# LCR.net
KiCad netlist of a schematic drawn in EAGLE
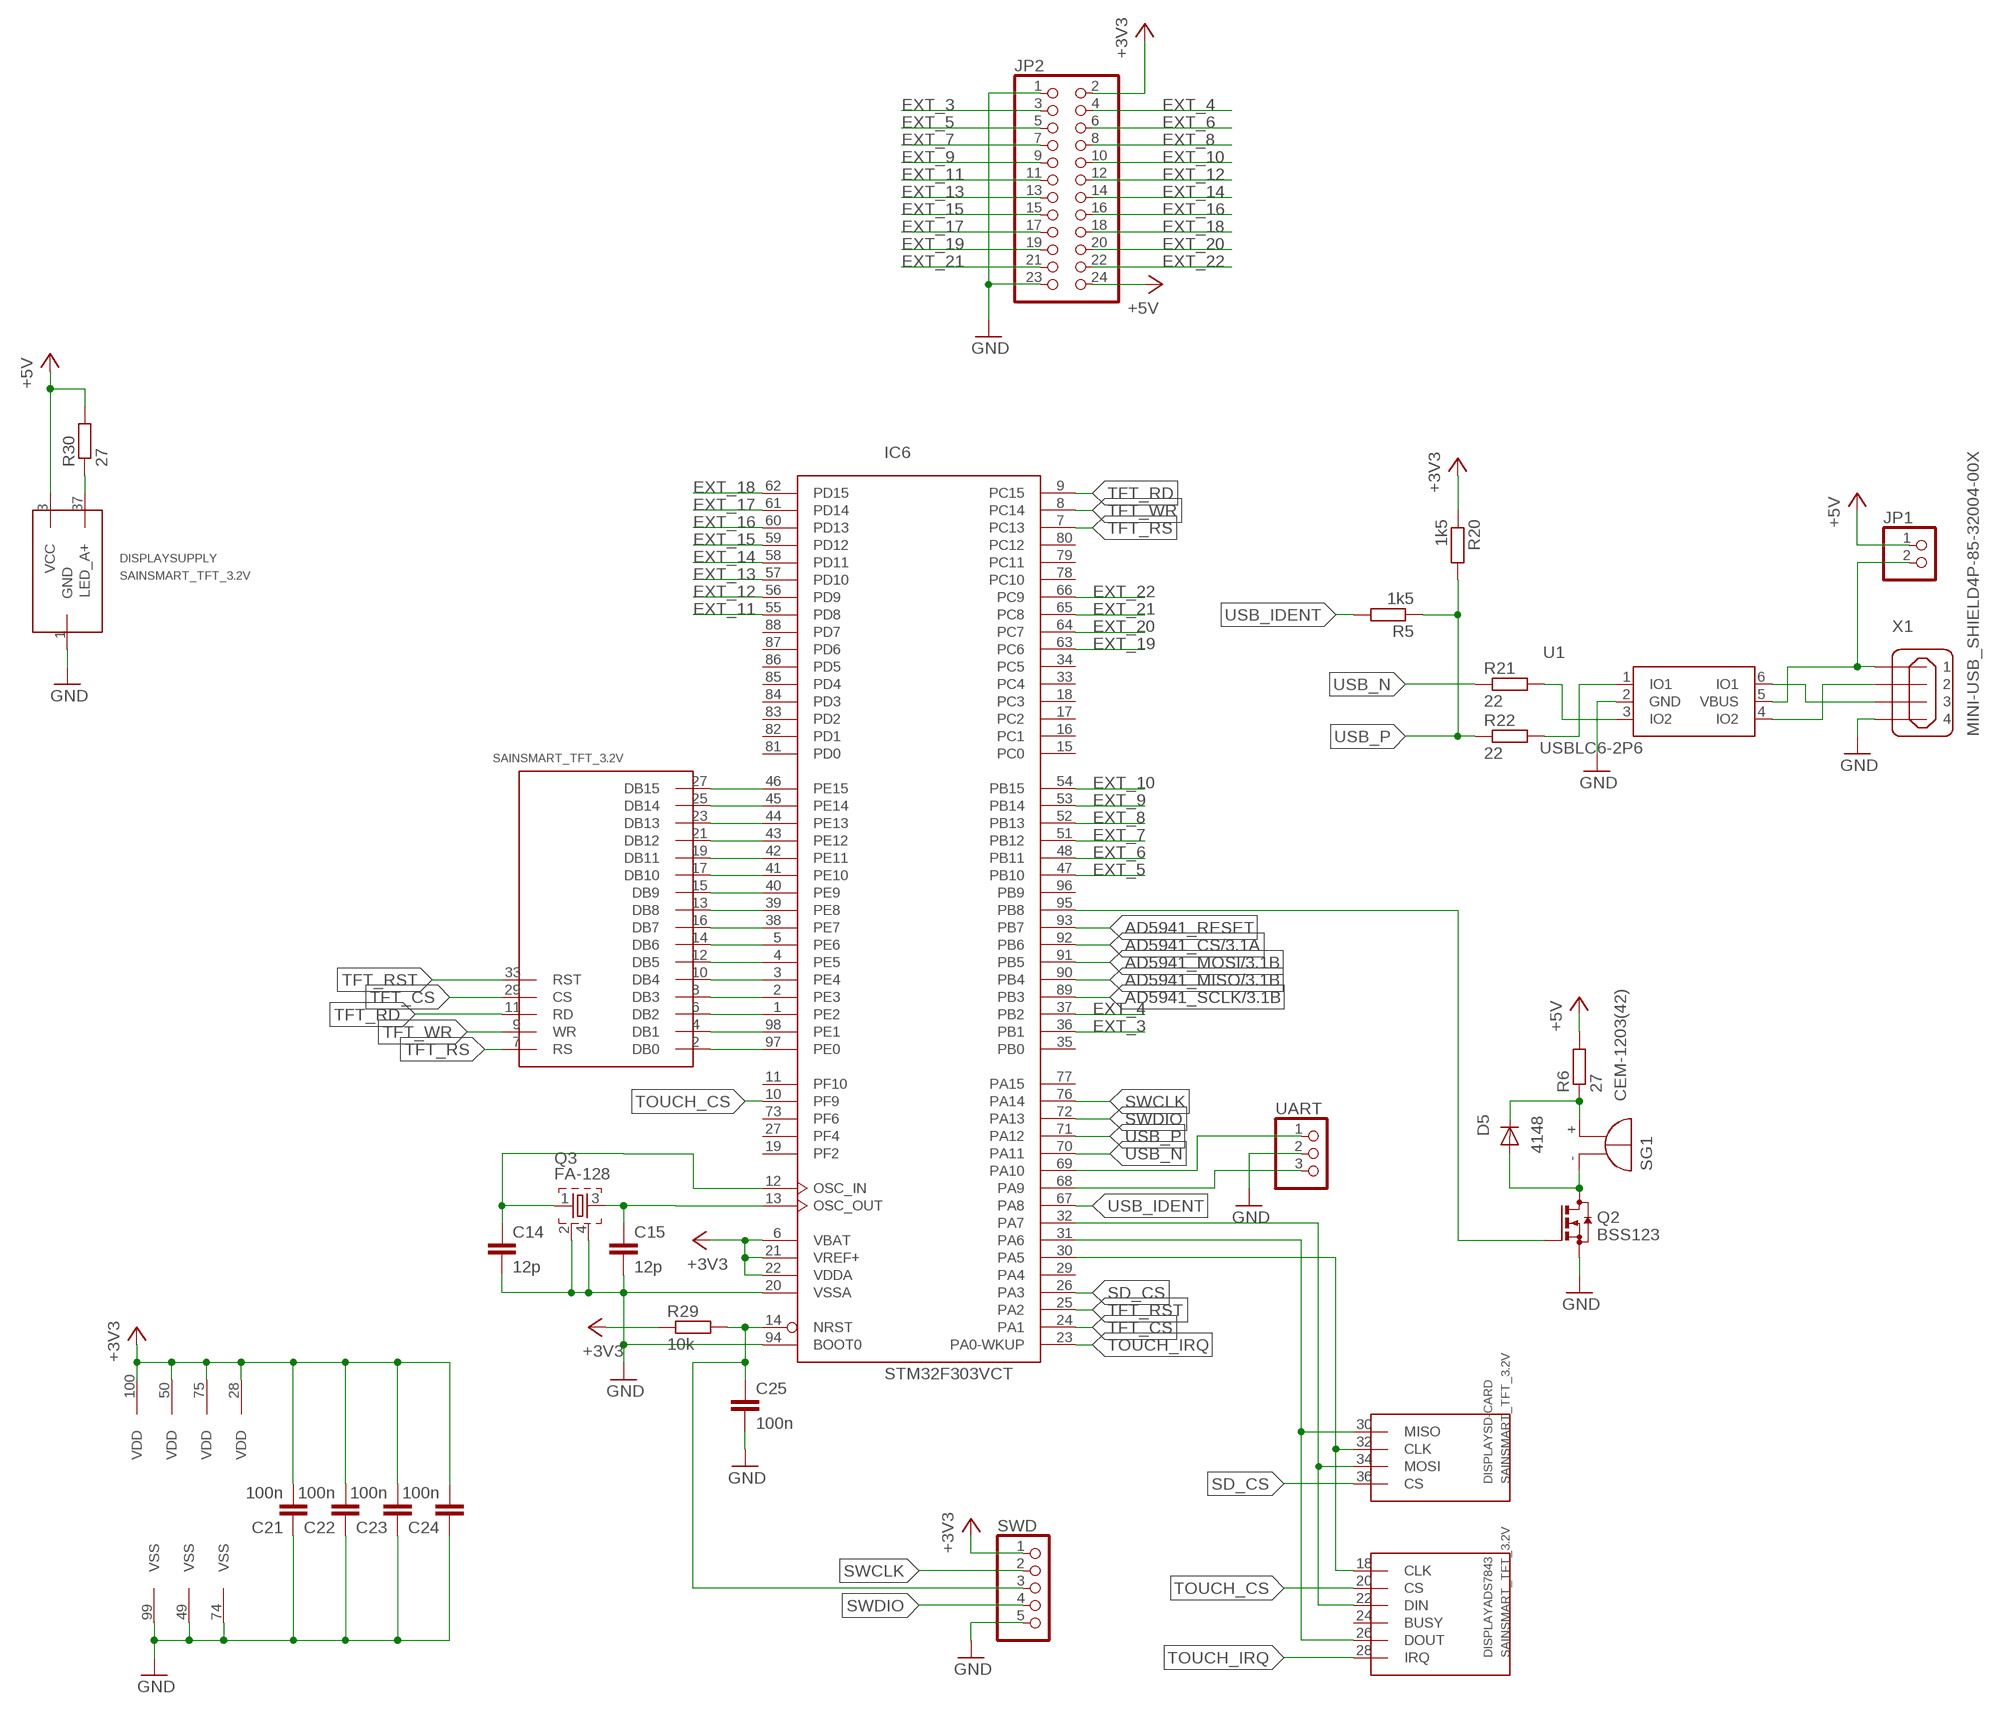
[diagram p0: schematic, sheet 1]
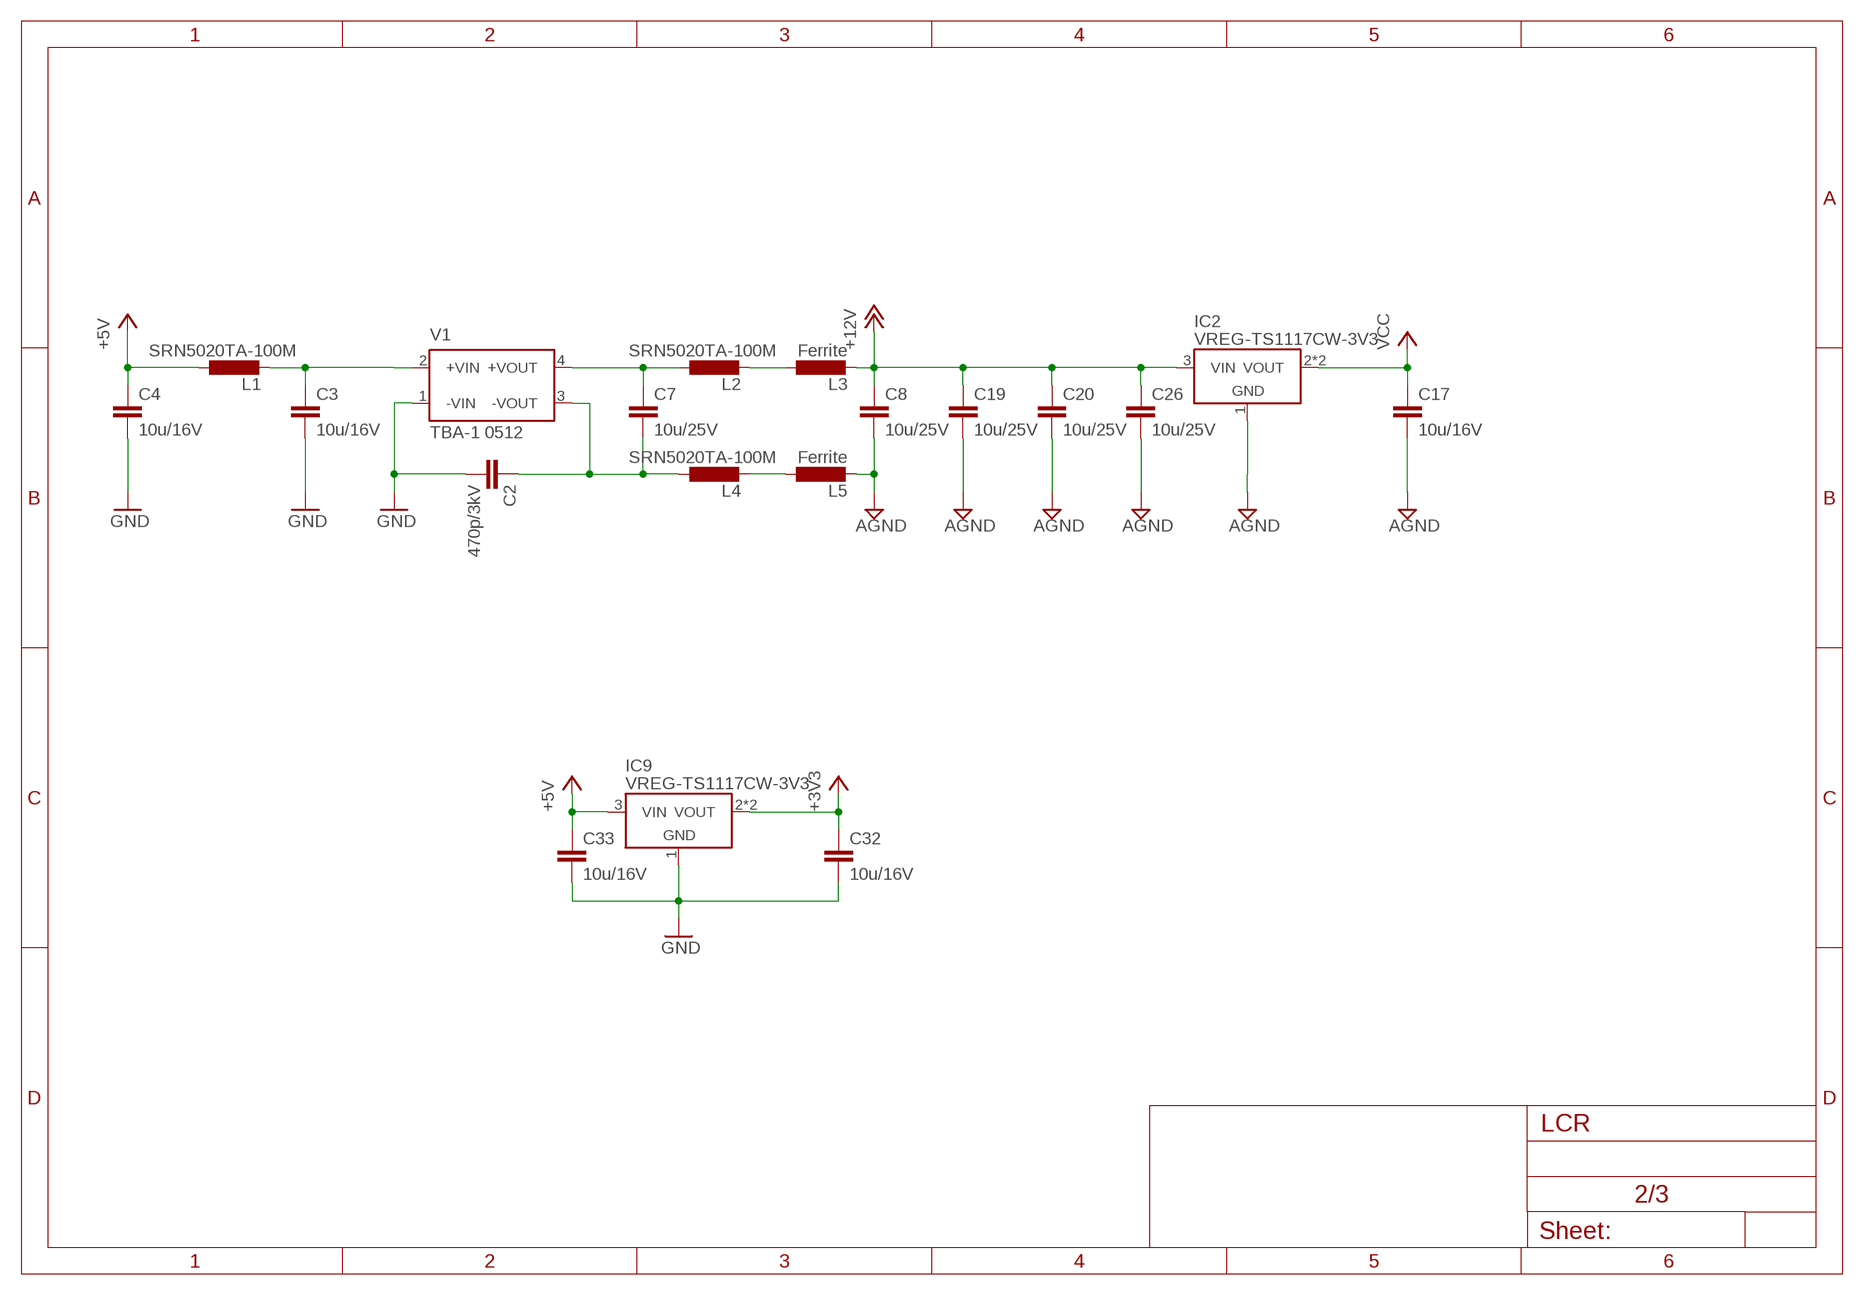
[diagram p1: schematic, sheet 2]
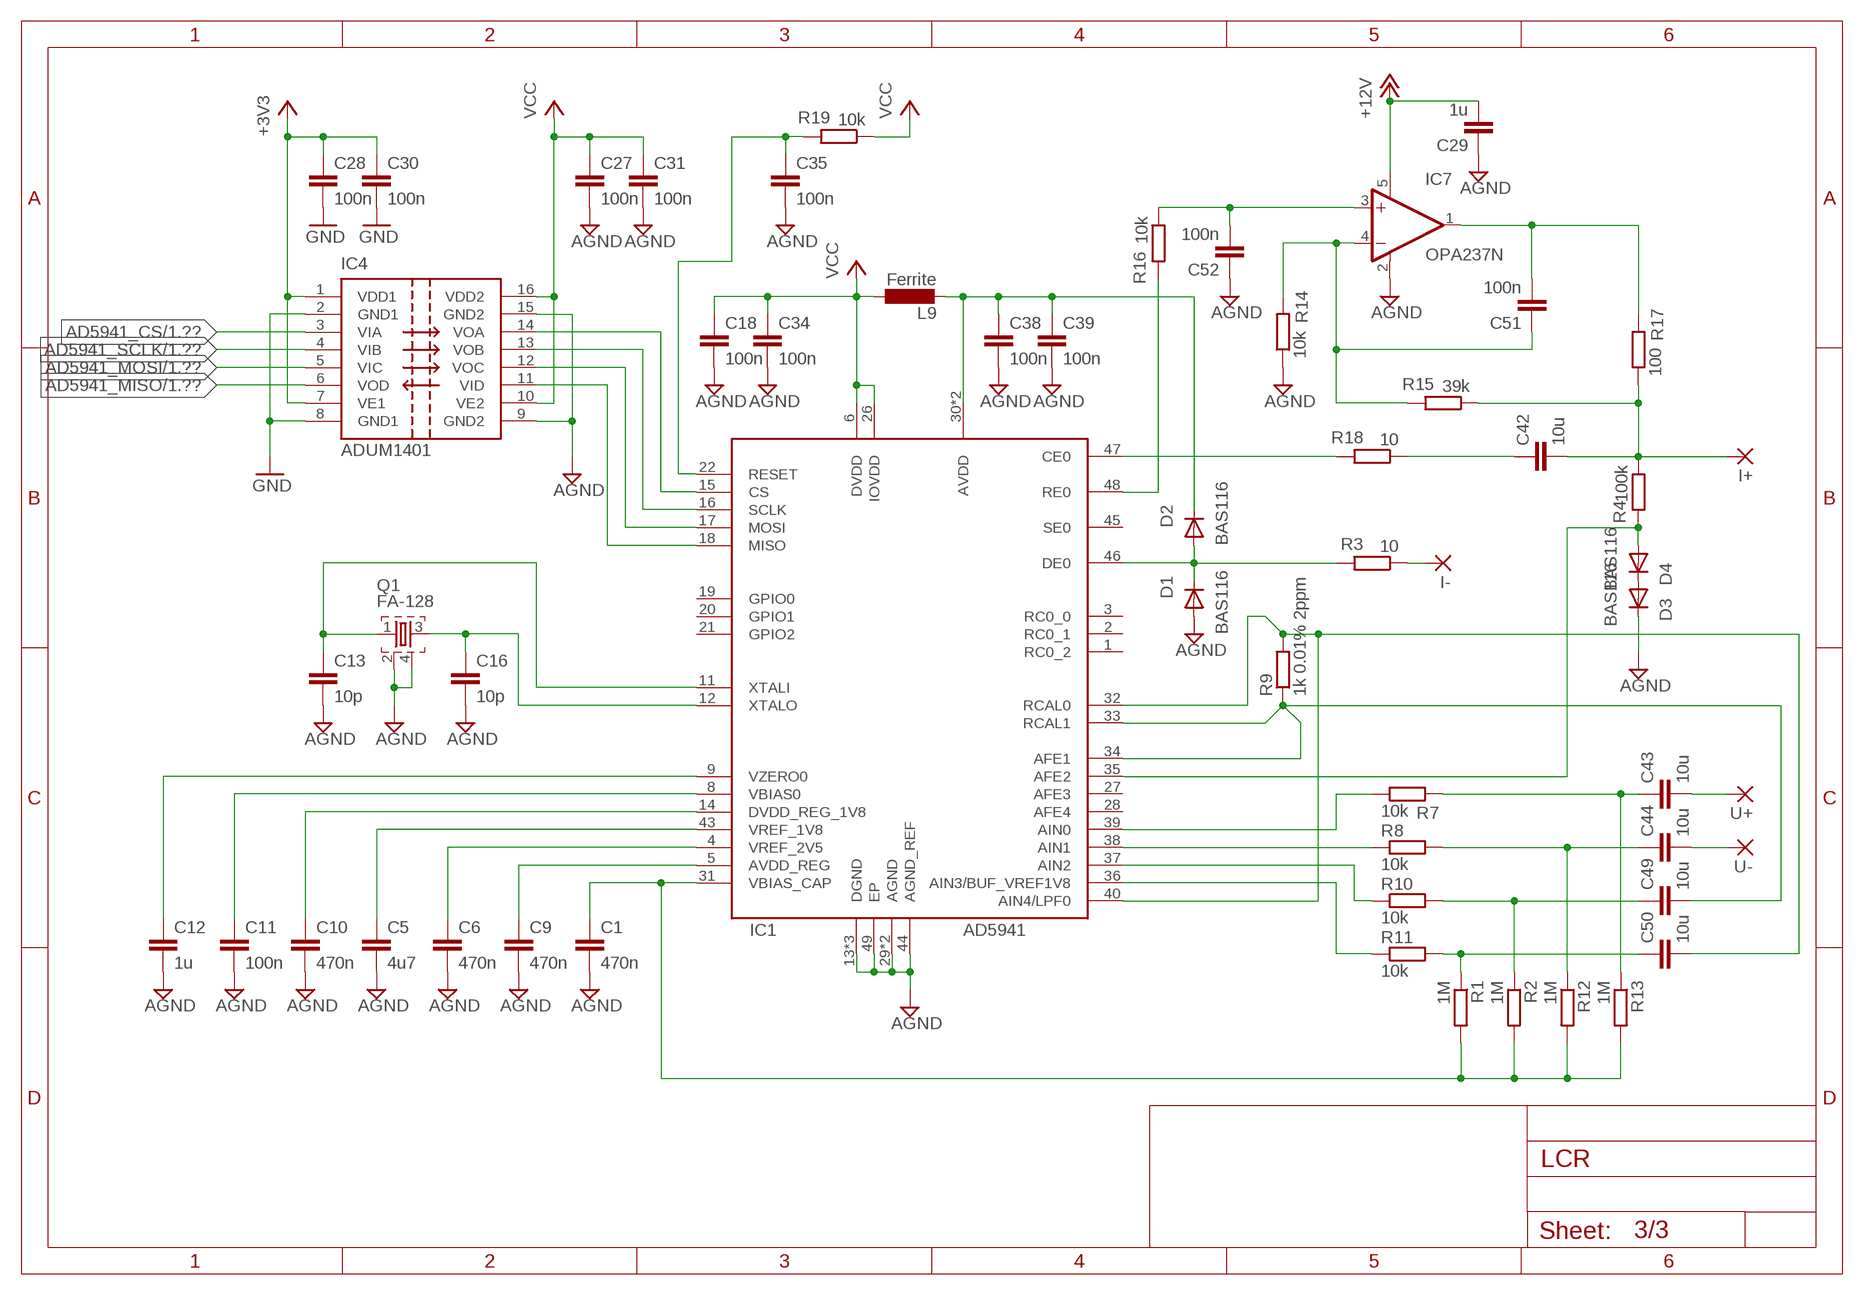
[diagram p2: schematic, sheet 3]

(export (version "E")
  (design (tool "Eeschema 10.0.6"))
  (components
    (comp (ref "C14")
      (value "12p")
      (footprint "eagle-import:C0603K")
      (libsource (lib "eagle-import") (part "C-EUC0603K"))
    )
    (comp (ref "C15")
      (value "12p")
      (footprint "eagle-import:C0603K")
      (libsource (lib "eagle-import") (part "C-EUC0603K"))
    )
    (comp (ref "C21")
      (value "100n")
      (footprint "eagle-import:C0603K")
      (libsource (lib "eagle-import") (part "C-EUC0603K"))
    )
    (comp (ref "C22")
      (value "100n")
      (footprint "eagle-import:C0603K")
      (libsource (lib "eagle-import") (part "C-EUC0603K"))
    )
    (comp (ref "C23")
      (value "100n")
      (footprint "eagle-import:C0603K")
      (libsource (lib "eagle-import") (part "C-EUC0603K"))
    )
    (comp (ref "C24")
      (value "100n")
      (footprint "eagle-import:C0603K")
      (libsource (lib "eagle-import") (part "C-EUC0603K"))
    )
    (comp (ref "C25")
      (value "100n")
      (footprint "eagle-import:C0603K")
      (libsource (lib "eagle-import") (part "C-EUC0603K"))
    )
    (comp (ref "D5")
      (value "4148")
      (footprint "eagle-import:SOD123")
      (libsource (lib "eagle-import") (part "DIODE-SOD123"))
    )
    (comp (ref "DISPLAY")
      (value "SAINSMART_TFT_3.2V")
      (footprint "eagle-import:SAINSMART_ANGLED")
      (libsource (lib "eagle-import") (part "SAINSMART_TFT_3.2V"))
    )
    (comp (ref "IC6")
      (value "STM32F303VCT")
      (footprint "eagle-import:LQFP100")
      (libsource (lib "eagle-import") (part "STM32F303VTC"))
    )
    (comp (ref "JP1")
      (value "PINHD-1X2")
      (footprint "eagle-import:1X02")
      (libsource (lib "eagle-import") (part "PINHD-1X2"))
    )
    (comp (ref "JP2")
      (value "PINHD-2X12")
      (footprint "eagle-import:2X12")
      (libsource (lib "eagle-import") (part "PINHD-2X12"))
    )
    (comp (ref "Q2")
      (value "BSS123")
      (footprint "eagle-import:SOT23")
      (libsource (lib "eagle-import") (part "BSS123"))
    )
    (comp (ref "Q3")
      (value "FA-128")
      (footprint "eagle-import:FA-128")
      (libsource (lib "eagle-import") (part "FA-128"))
    )
    (comp (ref "R5")
      (value "1k5")
      (footprint "eagle-import:R0603")
      (libsource (lib "eagle-import") (part "resistor_R-EU_R0603"))
    )
    (comp (ref "R6")
      (value "27")
      (footprint "eagle-import:R1206")
      (libsource (lib "eagle-import") (part "resistor_R-EU_R1206"))
    )
    (comp (ref "R20")
      (value "1k5")
      (footprint "eagle-import:R0603")
      (libsource (lib "eagle-import") (part "resistor_R-EU_R0603"))
    )
    (comp (ref "R21")
      (value "22")
      (footprint "eagle-import:R0603")
      (libsource (lib "eagle-import") (part "resistor_R-EU_R0603"))
    )
    (comp (ref "R22")
      (value "22")
      (footprint "eagle-import:R0603")
      (libsource (lib "eagle-import") (part "resistor_R-EU_R0603"))
    )
    (comp (ref "R29")
      (value "10k")
      (footprint "eagle-import:R0603")
      (libsource (lib "eagle-import") (part "resistor_R-EU_R0603"))
    )
    (comp (ref "R30")
      (value "27")
      (footprint "eagle-import:R1206")
      (libsource (lib "eagle-import") (part "resistor_R-EU_R1206"))
    )
    (comp (ref "SG1")
      (value "CEM-1203(42)")
      (footprint "eagle-import:F_QMBIII")
      (libsource (lib "eagle-import") (part "F/QMBIII"))
    )
    (comp (ref "SWD")
      (value "PINHD-1X5")
      (footprint "eagle-import:1X05")
      (libsource (lib "eagle-import") (part "PINHD-1X5"))
    )
    (comp (ref "U1")
      (value "USBLC6-2P6")
      (footprint "eagle-import:SOT23-6")
      (libsource (lib "eagle-import") (part "USBLC6-2P6"))
    )
    (comp (ref "UART")
      (value "PINHD-1X3")
      (footprint "eagle-import:1X03")
      (libsource (lib "eagle-import") (part "PINHD-1X3"))
    )
    (comp (ref "X1")
      (value "MINI-USB_SHIELD4P-85-32004-00X")
      (footprint "eagle-import:85-32004-00X")
      (libsource (lib "eagle-import") (part "MINI-USB_SHIELD4P-85-32004-00X"))
    )
    (comp (ref "C2")
      (value "470p/3kV")
      (footprint "eagle-import:C1812")
      (libsource (lib "eagle-import") (part "resistor_C-EUC1812"))
    )
    (comp (ref "C3")
      (value "10u/16V")
      (footprint "eagle-import:C1206K")
      (libsource (lib "eagle-import") (part "C-EUC1206K"))
    )
    (comp (ref "C4")
      (value "10u/16V")
      (footprint "eagle-import:C1206K")
      (libsource (lib "eagle-import") (part "C-EUC1206K"))
    )
    (comp (ref "C7")
      (value "10u/25V")
      (footprint "eagle-import:C1206K")
      (libsource (lib "eagle-import") (part "C-EUC1206K"))
    )
    (comp (ref "C8")
      (value "10u/25V")
      (footprint "eagle-import:C1206K")
      (libsource (lib "eagle-import") (part "C-EUC1206K"))
    )
    (comp (ref "C17")
      (value "10u/16V")
      (footprint "eagle-import:C1206K")
      (libsource (lib "eagle-import") (part "C-EUC1206K"))
    )
    (comp (ref "C19")
      (value "10u/25V")
      (footprint "eagle-import:C1206K")
      (libsource (lib "eagle-import") (part "C-EUC1206K"))
    )
    (comp (ref "C20")
      (value "10u/25V")
      (footprint "eagle-import:C1206K")
      (libsource (lib "eagle-import") (part "C-EUC1206K"))
    )
    (comp (ref "C26")
      (value "10u/25V")
      (footprint "eagle-import:C1206K")
      (libsource (lib "eagle-import") (part "C-EUC1206K"))
    )
    (comp (ref "C32")
      (value "10u/16V")
      (footprint "eagle-import:C1206K")
      (libsource (lib "eagle-import") (part "C-EUC1206K"))
    )
    (comp (ref "C33")
      (value "10u/16V")
      (footprint "eagle-import:C1206K")
      (libsource (lib "eagle-import") (part "C-EUC1206K"))
    )
    (comp (ref "IC2")
      (value "VREG-TS1117CW-3V3")
      (footprint "eagle-import:SOT223")
      (libsource (lib "eagle-import") (part "VREG-TS1117CW-3V3"))
    )
    (comp (ref "IC9")
      (value "VREG-TS1117CW-3V3")
      (footprint "eagle-import:SOT223")
      (libsource (lib "eagle-import") (part "VREG-TS1117CW-3V3"))
    )
    (comp (ref "L1")
      (value "SRN5020TA-100M")
      (footprint "eagle-import:SRN5040")
      (libsource (lib "eagle-import") (part "SRN5040"))
    )
    (comp (ref "L2")
      (value "SRN5020TA-100M")
      (footprint "eagle-import:SRN5040")
      (libsource (lib "eagle-import") (part "SRN5040"))
    )
    (comp (ref "L3")
      (value "Ferrite")
      (footprint "eagle-import:R0603")
      (libsource (lib "eagle-import") (part "INDUCTOR0603"))
    )
    (comp (ref "L4")
      (value "SRN5020TA-100M")
      (footprint "eagle-import:SRN5040")
      (libsource (lib "eagle-import") (part "SRN5040"))
    )
    (comp (ref "L5")
      (value "Ferrite")
      (footprint "eagle-import:R0603")
      (libsource (lib "eagle-import") (part "INDUCTOR0603"))
    )
    (comp (ref "V1")
      (value "TBA-1 0512")
      (footprint "eagle-import:TME")
      (fields (field (name "MPN") "TME 0505S"))
      (libsource (lib "eagle-import") (part "TME?0505S"))
    )
    (comp (ref "C1")
      (value "470n")
      (footprint "eagle-import:C0603K")
      (libsource (lib "eagle-import") (part "C-EUC0603K"))
    )
    (comp (ref "C5")
      (value "4u7")
      (footprint "eagle-import:C0603K")
      (libsource (lib "eagle-import") (part "C-EUC0603K"))
    )
    (comp (ref "C6")
      (value "470n")
      (footprint "eagle-import:C0603K")
      (libsource (lib "eagle-import") (part "C-EUC0603K"))
    )
    (comp (ref "C9")
      (value "470n")
      (footprint "eagle-import:C0603K")
      (libsource (lib "eagle-import") (part "C-EUC0603K"))
    )
    (comp (ref "C10")
      (value "470n")
      (footprint "eagle-import:C0603K")
      (libsource (lib "eagle-import") (part "C-EUC0603K"))
    )
    (comp (ref "C11")
      (value "100n")
      (footprint "eagle-import:C0603K")
      (libsource (lib "eagle-import") (part "C-EUC0603K"))
    )
    (comp (ref "C12")
      (value "1u")
      (footprint "eagle-import:C0603K")
      (libsource (lib "eagle-import") (part "C-EUC0603K"))
    )
    (comp (ref "C13")
      (value "10p")
      (footprint "eagle-import:C0603K")
      (libsource (lib "eagle-import") (part "C-EUC0603K"))
    )
    (comp (ref "C16")
      (value "10p")
      (footprint "eagle-import:C0603K")
      (libsource (lib "eagle-import") (part "C-EUC0603K"))
    )
    (comp (ref "C18")
      (value "100n")
      (footprint "eagle-import:C0603K")
      (libsource (lib "eagle-import") (part "C-EUC0603K"))
    )
    (comp (ref "C27")
      (value "100n")
      (footprint "eagle-import:C0603K")
      (libsource (lib "eagle-import") (part "C-EUC0603K"))
    )
    (comp (ref "C28")
      (value "100n")
      (footprint "eagle-import:C0603K")
      (libsource (lib "eagle-import") (part "C-EUC0603K"))
    )
    (comp (ref "C29")
      (value "1u")
      (footprint "eagle-import:C0603K")
      (libsource (lib "eagle-import") (part "C-EUC0603K"))
    )
    (comp (ref "C30")
      (value "100n")
      (footprint "eagle-import:C0603K")
      (libsource (lib "eagle-import") (part "C-EUC0603K"))
    )
    (comp (ref "C31")
      (value "100n")
      (footprint "eagle-import:C0603K")
      (libsource (lib "eagle-import") (part "C-EUC0603K"))
    )
    (comp (ref "C34")
      (value "100n")
      (footprint "eagle-import:C0603K")
      (libsource (lib "eagle-import") (part "C-EUC0603K"))
    )
    (comp (ref "C35")
      (value "100n")
      (footprint "eagle-import:C0603K")
      (libsource (lib "eagle-import") (part "C-EUC0603K"))
    )
    (comp (ref "C38")
      (value "100n")
      (footprint "eagle-import:C0603K")
      (libsource (lib "eagle-import") (part "C-EUC0603K"))
    )
    (comp (ref "C39")
      (value "100n")
      (footprint "eagle-import:C0603K")
      (libsource (lib "eagle-import") (part "C-EUC0603K"))
    )
    (comp (ref "C42")
      (value "10u")
      (footprint "eagle-import:C1206K")
      (libsource (lib "eagle-import") (part "resistor_C-EUC1206K"))
    )
    (comp (ref "C43")
      (value "10u")
      (footprint "eagle-import:C1206K")
      (libsource (lib "eagle-import") (part "resistor_C-EUC1206K"))
    )
    (comp (ref "C44")
      (value "10u")
      (footprint "eagle-import:C1206K")
      (libsource (lib "eagle-import") (part "resistor_C-EUC1206K"))
    )
    (comp (ref "C49")
      (value "10u")
      (footprint "eagle-import:C1206K")
      (libsource (lib "eagle-import") (part "resistor_C-EUC1206K"))
    )
    (comp (ref "C50")
      (value "10u")
      (footprint "eagle-import:C1206K")
      (libsource (lib "eagle-import") (part "resistor_C-EUC1206K"))
    )
    (comp (ref "C51")
      (value "100n")
      (footprint "eagle-import:C0603K")
      (libsource (lib "eagle-import") (part "C-EUC0603K"))
    )
    (comp (ref "C52")
      (value "100n")
      (footprint "eagle-import:C0603K")
      (libsource (lib "eagle-import") (part "C-EUC0603K"))
    )
    (comp (ref "D1")
      (value "BAS116")
      (footprint "eagle-import:SOD123")
      (libsource (lib "eagle-import") (part "DIODE-SOD123"))
    )
    (comp (ref "D2")
      (value "BAS116")
      (footprint "eagle-import:SOD123")
      (libsource (lib "eagle-import") (part "DIODE-SOD123"))
    )
    (comp (ref "D3")
      (value "BAS116")
      (footprint "eagle-import:SOD123")
      (libsource (lib "eagle-import") (part "DIODE-SOD123"))
    )
    (comp (ref "D4")
      (value "BAS116")
      (footprint "eagle-import:SOD123")
      (libsource (lib "eagle-import") (part "DIODE-SOD123"))
    )
    (comp (ref "I+")
      (value "2,54/1,1")
      (footprint "eagle-import:2,54_1,1")
      (libsource (lib "eagle-import") (part "2,54/1,1"))
    )
    (comp (ref "I-")
      (value "2,54/1,1")
      (footprint "eagle-import:2,54_1,1")
      (libsource (lib "eagle-import") (part "2,54/1,1"))
    )
    (comp (ref "IC1")
      (value "AD5941")
      (footprint "eagle-import:QFN50P700X700X80-49T510N")
      (libsource (lib "eagle-import") (part "AD5941"))
    )
    (comp (ref "IC4")
      (value "ADUM1401")
      (footprint "eagle-import:SO16W")
      (libsource (lib "eagle-import") (part "ADUM1401"))
    )
    (comp (ref "IC7")
      (value "OPA237N")
      (footprint "eagle-import:SOT23-5")
      (fields (field (name "MF") "TEXAS INSTRUMENTS") (field (name "MPN") "OPA237NA/250"))
      (libsource (lib "eagle-import") (part "OPA237N"))
    )
    (comp (ref "L9")
      (value "Ferrite")
      (footprint "eagle-import:R0603")
      (libsource (lib "eagle-import") (part "INDUCTOR0603"))
    )
    (comp (ref "Q1")
      (value "FA-128")
      (footprint "eagle-import:FA-128")
      (libsource (lib "eagle-import") (part "FA-128"))
    )
    (comp (ref "R1")
      (value "1M")
      (footprint "eagle-import:R0603")
      (libsource (lib "eagle-import") (part "R-EU_R0603"))
    )
    (comp (ref "R2")
      (value "1M")
      (footprint "eagle-import:R0603")
      (libsource (lib "eagle-import") (part "R-EU_R0603"))
    )
    (comp (ref "R3")
      (value "10")
      (footprint "eagle-import:R0603")
      (libsource (lib "eagle-import") (part "R-EU_R0603"))
    )
    (comp (ref "R4")
      (value "100k")
      (footprint "eagle-import:R0603")
      (libsource (lib "eagle-import") (part "R-EU_R0603"))
    )
    (comp (ref "R7")
      (value "10k")
      (footprint "eagle-import:R0603")
      (libsource (lib "eagle-import") (part "R-EU_R0603"))
    )
    (comp (ref "R8")
      (value "10k")
      (footprint "eagle-import:R0603")
      (libsource (lib "eagle-import") (part "R-EU_R0603"))
    )
    (comp (ref "R9")
      (value "1k 0.01% 2ppm")
      (footprint "eagle-import:M0805")
      (libsource (lib "eagle-import") (part "resistor_R-EU_M0805"))
    )
    (comp (ref "R10")
      (value "10k")
      (footprint "eagle-import:R0603")
      (libsource (lib "eagle-import") (part "R-EU_R0603"))
    )
    (comp (ref "R11")
      (value "10k")
      (footprint "eagle-import:R0603")
      (libsource (lib "eagle-import") (part "R-EU_R0603"))
    )
    (comp (ref "R12")
      (value "1M")
      (footprint "eagle-import:R0603")
      (libsource (lib "eagle-import") (part "R-EU_R0603"))
    )
    (comp (ref "R13")
      (value "1M")
      (footprint "eagle-import:R0603")
      (libsource (lib "eagle-import") (part "R-EU_R0603"))
    )
    (comp (ref "R14")
      (value "10k")
      (footprint "eagle-import:R0603")
      (libsource (lib "eagle-import") (part "R-EU_R0603"))
    )
    (comp (ref "R15")
      (value "39k")
      (footprint "eagle-import:R0603")
      (libsource (lib "eagle-import") (part "R-EU_R0603"))
    )
    (comp (ref "R16")
      (value "10k")
      (footprint "eagle-import:R0603")
      (libsource (lib "eagle-import") (part "R-EU_R0603"))
    )
    (comp (ref "R17")
      (value "100")
      (footprint "eagle-import:R0603")
      (libsource (lib "eagle-import") (part "R-EU_R0603"))
    )
    (comp (ref "R18")
      (value "10")
      (footprint "eagle-import:R0603")
      (libsource (lib "eagle-import") (part "R-EU_R0603"))
    )
    (comp (ref "R19")
      (value "10k")
      (footprint "eagle-import:R0603")
      (libsource (lib "eagle-import") (part "R-EU_R0603"))
    )
    (comp (ref "U+")
      (value "2,54/1,1")
      (footprint "eagle-import:2,54_1,1")
      (libsource (lib "eagle-import") (part "2,54/1,1"))
    )
    (comp (ref "U-")
      (value "2,54/1,1")
      (footprint "eagle-import:2,54_1,1")
      (libsource (lib "eagle-import") (part "2,54/1,1"))
    )
  )
  (nets
    (net (code "1") (name "+3V3") (class "Default")
      (node (ref "C21") (pin "2") (pinfunction "2_2") (pintype "passive"))
      (node (ref "C22") (pin "2") (pinfunction "2_2") (pintype "passive"))
      (node (ref "C23") (pin "2") (pinfunction "2_2") (pintype "passive"))
      (node (ref "C24") (pin "2") (pinfunction "2_2") (pintype "passive"))
      (node (ref "C28") (pin "1") (pinfunction "1_1") (pintype "passive"))
      (node (ref "C30") (pin "1") (pinfunction "1_1") (pintype "passive"))
      (node (ref "C32") (pin "1") (pinfunction "1_1") (pintype "passive"))
      (node (ref "IC4") (pin "1") (pinfunction "VDD1_1") (pintype "power_in"))
      (node (ref "IC4") (pin "7") (pinfunction "VE1_7") (pintype "passive"))
      (node (ref "IC6") (pin "100") (pinfunction "VDD_100") (pintype "power_in"))
      (node (ref "IC6") (pin "21") (pinfunction "VREF+_21") (pintype "power_in"))
      (node (ref "IC6") (pin "22") (pinfunction "VDDA_22") (pintype "power_in"))
      (node (ref "IC6") (pin "28") (pinfunction "VDD_28") (pintype "power_in"))
      (node (ref "IC6") (pin "50") (pinfunction "VDD_50") (pintype "power_in"))
      (node (ref "IC6") (pin "6") (pinfunction "VBAT_6") (pintype "power_in"))
      (node (ref "IC6") (pin "75") (pinfunction "VDD_75") (pintype "power_in"))
      (node (ref "IC9") (pin "2") (pinfunction "VOUT_2") (pintype "power_in"))
      (node (ref "IC9") (pin "4") (pinfunction "VOUT_4") (pintype "power_in"))
      (node (ref "JP2") (pin "2") (pinfunction "2_2") (pintype "passive"))
      (node (ref "R20") (pin "1") (pinfunction "1_1") (pintype "passive"))
      (node (ref "R29") (pin "1") (pinfunction "1_1") (pintype "passive"))
      (node (ref "SWD") (pin "1") (pinfunction "1_1") (pintype "passive"))
    )
    (net (code "2") (name "+5V") (class "Default")
      (node (ref "C33") (pin "1") (pinfunction "1_1") (pintype "passive"))
      (node (ref "C4") (pin "1") (pinfunction "1_1") (pintype "passive"))
      (node (ref "DISPLAY") (pin "3") (pinfunction "VCC_3") (pintype "bidirectional"))
      (node (ref "IC9") (pin "3") (pinfunction "VIN_3") (pintype "power_in"))
      (node (ref "JP1") (pin "1") (pinfunction "1_1") (pintype "passive"))
      (node (ref "JP2") (pin "24") (pinfunction "24_24") (pintype "passive"))
      (node (ref "L1") (pin "P$1") (pinfunction "1_P$1") (pintype "passive"))
      (node (ref "R30") (pin "2") (pinfunction "2_2") (pintype "passive"))
      (node (ref "R6") (pin "2") (pinfunction "2_2") (pintype "passive"))
    )
    (net (code "3") (name "+12V") (class "Default")
      (node (ref "C19") (pin "1") (pinfunction "1_1") (pintype "passive"))
      (node (ref "C20") (pin "1") (pinfunction "1_1") (pintype "passive"))
      (node (ref "C26") (pin "1") (pinfunction "1_1") (pintype "passive"))
      (node (ref "C29") (pin "2") (pinfunction "2_2") (pintype "passive"))
      (node (ref "C8") (pin "1") (pinfunction "1_1") (pintype "passive"))
      (node (ref "IC2") (pin "3") (pinfunction "VIN_3") (pintype "power_in"))
      (node (ref "IC7") (pin "5") (pinfunction "V+_5") (pintype "power_in"))
      (node (ref "L3") (pin "2") (pinfunction "2_2") (pintype "passive"))
    )
    (net (code "4") (name "AD5941_CS") (class "Default")
      (node (ref "IC4") (pin "3") (pinfunction "VIA_3") (pintype "input"))
      (node (ref "IC6") (pin "92") (pinfunction "PB6_92") (pintype "bidirectional"))
    )
    (net (code "5") (name "AD5941_MISO") (class "Default")
      (node (ref "IC4") (pin "6") (pinfunction "VOD_6") (pintype "output"))
      (node (ref "IC6") (pin "90") (pinfunction "PB4_90") (pintype "bidirectional"))
    )
    (net (code "6") (name "AD5941_MOSI") (class "Default")
      (node (ref "IC4") (pin "5") (pinfunction "VIC_5") (pintype "input"))
      (node (ref "IC6") (pin "91") (pinfunction "PB5_91") (pintype "bidirectional"))
    )
    (net (code "7") (name "AD5941_RESET") (class "Default")
      (node (ref "IC6") (pin "93") (pinfunction "PB7_93") (pintype "bidirectional"))
    )
    (net (code "8") (name "AD5941_SCLK") (class "Default")
      (node (ref "IC4") (pin "4") (pinfunction "VIB_4") (pintype "input"))
      (node (ref "IC6") (pin "89") (pinfunction "PB3_89") (pintype "bidirectional"))
    )
    (net (code "9") (name "AGND") (class "Default")
      (node (ref "C1") (pin "2") (pinfunction "2_2") (pintype "passive"))
      (node (ref "C10") (pin "2") (pinfunction "2_2") (pintype "passive"))
      (node (ref "C11") (pin "2") (pinfunction "2_2") (pintype "passive"))
      (node (ref "C12") (pin "2") (pinfunction "2_2") (pintype "passive"))
      (node (ref "C13") (pin "2") (pinfunction "2_2") (pintype "passive"))
      (node (ref "C16") (pin "2") (pinfunction "2_2") (pintype "passive"))
      (node (ref "C17") (pin "2") (pinfunction "2_2") (pintype "passive"))
      (node (ref "C18") (pin "2") (pinfunction "2_2") (pintype "passive"))
      (node (ref "C19") (pin "2") (pinfunction "2_2") (pintype "passive"))
      (node (ref "C20") (pin "2") (pinfunction "2_2") (pintype "passive"))
      (node (ref "C26") (pin "2") (pinfunction "2_2") (pintype "passive"))
      (node (ref "C27") (pin "2") (pinfunction "2_2") (pintype "passive"))
      (node (ref "C29") (pin "1") (pinfunction "1_1") (pintype "passive"))
      (node (ref "C31") (pin "2") (pinfunction "2_2") (pintype "passive"))
      (node (ref "C34") (pin "2") (pinfunction "2_2") (pintype "passive"))
      (node (ref "C35") (pin "2") (pinfunction "2_2") (pintype "passive"))
      (node (ref "C38") (pin "2") (pinfunction "2_2") (pintype "passive"))
      (node (ref "C39") (pin "2") (pinfunction "2_2") (pintype "passive"))
      (node (ref "C5") (pin "2") (pinfunction "2_2") (pintype "passive"))
      (node (ref "C52") (pin "1") (pinfunction "1_1") (pintype "passive"))
      (node (ref "C6") (pin "2") (pinfunction "2_2") (pintype "passive"))
      (node (ref "C8") (pin "2") (pinfunction "2_2") (pintype "passive"))
      (node (ref "C9") (pin "2") (pinfunction "2_2") (pintype "passive"))
      (node (ref "D1") (pin "A") (pinfunction "A_A") (pintype "passive"))
      (node (ref "D3") (pin "C") (pinfunction "C_C") (pintype "passive"))
      (node (ref "IC1") (pin "13") (pinfunction "DGND_13") (pintype "bidirectional"))
      (node (ref "IC1") (pin "23") (pinfunction "DGND_23") (pintype "bidirectional"))
      (node (ref "IC1") (pin "25") (pinfunction "DGND_25") (pintype "bidirectional"))
      (node (ref "IC1") (pin "29") (pinfunction "AGND_29") (pintype "bidirectional"))
      (node (ref "IC1") (pin "42") (pinfunction "AGND_42") (pintype "bidirectional"))
      (node (ref "IC1") (pin "44") (pinfunction "AGND_REF_44") (pintype "bidirectional"))
      (node (ref "IC1") (pin "49") (pinfunction "EP_49") (pintype "bidirectional"))
      (node (ref "IC2") (pin "1") (pinfunction "GND_1") (pintype "power_in"))
      (node (ref "IC4") (pin "15") (pinfunction "GND2_15") (pintype "power_in"))
      (node (ref "IC4") (pin "9") (pinfunction "GND2_9") (pintype "power_in"))
      (node (ref "IC7") (pin "2") (pinfunction "V-_2") (pintype "power_in"))
      (node (ref "L5") (pin "2") (pinfunction "2_2") (pintype "passive"))
      (node (ref "Q1") (pin "2") (pinfunction "2_2") (pintype "passive"))
      (node (ref "Q1") (pin "4") (pinfunction "4_4") (pintype "passive"))
      (node (ref "R14") (pin "1") (pinfunction "1_1") (pintype "passive"))
    )
    (net (code "10") (name "EXT_3") (class "Default")
      (node (ref "IC6") (pin "36") (pinfunction "PB1_36") (pintype "bidirectional"))
      (node (ref "JP2") (pin "3") (pinfunction "3_3") (pintype "passive"))
    )
    (net (code "11") (name "EXT_4") (class "Default")
      (node (ref "IC6") (pin "37") (pinfunction "PB2_37") (pintype "bidirectional"))
      (node (ref "JP2") (pin "4") (pinfunction "4_4") (pintype "passive"))
    )
    (net (code "12") (name "EXT_5") (class "Default")
      (node (ref "IC6") (pin "47") (pinfunction "PB10_47") (pintype "bidirectional"))
      (node (ref "JP2") (pin "5") (pinfunction "5_5") (pintype "passive"))
    )
    (net (code "13") (name "EXT_6") (class "Default")
      (node (ref "IC6") (pin "48") (pinfunction "PB11_48") (pintype "bidirectional"))
      (node (ref "JP2") (pin "6") (pinfunction "6_6") (pintype "passive"))
    )
    (net (code "14") (name "EXT_7") (class "Default")
      (node (ref "IC6") (pin "51") (pinfunction "PB12_51") (pintype "bidirectional"))
      (node (ref "JP2") (pin "7") (pinfunction "7_7") (pintype "passive"))
    )
    (net (code "15") (name "EXT_8") (class "Default")
      (node (ref "IC6") (pin "52") (pinfunction "PB13_52") (pintype "bidirectional"))
      (node (ref "JP2") (pin "8") (pinfunction "8_8") (pintype "passive"))
    )
    (net (code "16") (name "EXT_9") (class "Default")
      (node (ref "IC6") (pin "53") (pinfunction "PB14_53") (pintype "bidirectional"))
      (node (ref "JP2") (pin "9") (pinfunction "9_9") (pintype "passive"))
    )
    (net (code "17") (name "EXT_10") (class "Default")
      (node (ref "IC6") (pin "54") (pinfunction "PB15_54") (pintype "bidirectional"))
      (node (ref "JP2") (pin "10") (pinfunction "10_10") (pintype "passive"))
    )
    (net (code "18") (name "EXT_11") (class "Default")
      (node (ref "IC6") (pin "55") (pinfunction "PD8_55") (pintype "bidirectional"))
      (node (ref "JP2") (pin "11") (pinfunction "11_11") (pintype "passive"))
    )
    (net (code "19") (name "EXT_12") (class "Default")
      (node (ref "IC6") (pin "56") (pinfunction "PD9_56") (pintype "bidirectional"))
      (node (ref "JP2") (pin "12") (pinfunction "12_12") (pintype "passive"))
    )
    (net (code "20") (name "EXT_13") (class "Default")
      (node (ref "IC6") (pin "57") (pinfunction "PD10_57") (pintype "bidirectional"))
      (node (ref "JP2") (pin "13") (pinfunction "13_13") (pintype "passive"))
    )
    (net (code "21") (name "EXT_14") (class "Default")
      (node (ref "IC6") (pin "58") (pinfunction "PD11_58") (pintype "bidirectional"))
      (node (ref "JP2") (pin "14") (pinfunction "14_14") (pintype "passive"))
    )
    (net (code "22") (name "EXT_15") (class "Default")
      (node (ref "IC6") (pin "59") (pinfunction "PD12_59") (pintype "bidirectional"))
      (node (ref "JP2") (pin "15") (pinfunction "15_15") (pintype "passive"))
    )
    (net (code "23") (name "EXT_16") (class "Default")
      (node (ref "IC6") (pin "60") (pinfunction "PD13_60") (pintype "bidirectional"))
      (node (ref "JP2") (pin "16") (pinfunction "16_16") (pintype "passive"))
    )
    (net (code "24") (name "EXT_17") (class "Default")
      (node (ref "IC6") (pin "61") (pinfunction "PD14_61") (pintype "bidirectional"))
      (node (ref "JP2") (pin "17") (pinfunction "17_17") (pintype "passive"))
    )
    (net (code "25") (name "EXT_18") (class "Default")
      (node (ref "IC6") (pin "62") (pinfunction "PD15_62") (pintype "bidirectional"))
      (node (ref "JP2") (pin "18") (pinfunction "18_18") (pintype "passive"))
    )
    (net (code "26") (name "EXT_19") (class "Default")
      (node (ref "IC6") (pin "63") (pinfunction "PC6_63") (pintype "bidirectional"))
      (node (ref "JP2") (pin "19") (pinfunction "19_19") (pintype "passive"))
    )
    (net (code "27") (name "EXT_20") (class "Default")
      (node (ref "IC6") (pin "64") (pinfunction "PC7_64") (pintype "bidirectional"))
      (node (ref "JP2") (pin "20") (pinfunction "20_20") (pintype "passive"))
    )
    (net (code "28") (name "EXT_21") (class "Default")
      (node (ref "IC6") (pin "65") (pinfunction "PC8_65") (pintype "bidirectional"))
      (node (ref "JP2") (pin "21") (pinfunction "21_21") (pintype "passive"))
    )
    (net (code "29") (name "EXT_22") (class "Default")
      (node (ref "IC6") (pin "66") (pinfunction "PC9_66") (pintype "bidirectional"))
      (node (ref "JP2") (pin "22") (pinfunction "22_22") (pintype "passive"))
    )
    (net (code "30") (name "GND") (class "Default")
      (node (ref "C14") (pin "2") (pinfunction "2_2") (pintype "passive"))
      (node (ref "C15") (pin "2") (pinfunction "2_2") (pintype "passive"))
      (node (ref "C2") (pin "2") (pinfunction "2_2") (pintype "passive"))
      (node (ref "C21") (pin "1") (pinfunction "1_1") (pintype "passive"))
      (node (ref "C22") (pin "1") (pinfunction "1_1") (pintype "passive"))
      (node (ref "C23") (pin "1") (pinfunction "1_1") (pintype "passive"))
      (node (ref "C24") (pin "1") (pinfunction "1_1") (pintype "passive"))
      (node (ref "C25") (pin "2") (pinfunction "2_2") (pintype "passive"))
      (node (ref "C28") (pin "2") (pinfunction "2_2") (pintype "passive"))
      (node (ref "C3") (pin "2") (pinfunction "2_2") (pintype "passive"))
      (node (ref "C30") (pin "2") (pinfunction "2_2") (pintype "passive"))
      (node (ref "C32") (pin "2") (pinfunction "2_2") (pintype "passive"))
      (node (ref "C33") (pin "2") (pinfunction "2_2") (pintype "passive"))
      (node (ref "C4") (pin "2") (pinfunction "2_2") (pintype "passive"))
      (node (ref "DISPLAY") (pin "1") (pinfunction "GND_1") (pintype "bidirectional"))
      (node (ref "IC4") (pin "2") (pinfunction "GND1_2") (pintype "power_in"))
      (node (ref "IC4") (pin "8") (pinfunction "GND1_8") (pintype "power_in"))
      (node (ref "IC6") (pin "20") (pinfunction "VSSA_20") (pintype "power_in"))
      (node (ref "IC6") (pin "49") (pinfunction "VSS_49") (pintype "power_in"))
      (node (ref "IC6") (pin "74") (pinfunction "VSS_74") (pintype "power_in"))
      (node (ref "IC6") (pin "94") (pinfunction "BOOT0_94") (pintype "input"))
      (node (ref "IC6") (pin "99") (pinfunction "VSS_99") (pintype "power_in"))
      (node (ref "IC9") (pin "1") (pinfunction "GND_1") (pintype "power_in"))
      (node (ref "JP2") (pin "1") (pinfunction "1_1") (pintype "passive"))
      (node (ref "JP2") (pin "23") (pinfunction "23_23") (pintype "passive"))
      (node (ref "Q2") (pin "2") (pinfunction "S_2") (pintype "passive"))
      (node (ref "Q3") (pin "2") (pinfunction "2_2") (pintype "passive"))
      (node (ref "Q3") (pin "4") (pinfunction "4_4") (pintype "passive"))
      (node (ref "SWD") (pin "5") (pinfunction "5_5") (pintype "passive"))
      (node (ref "U1") (pin "2") (pinfunction "GND_2") (pintype "power_in"))
      (node (ref "UART") (pin "2") (pinfunction "2_2") (pintype "passive"))
      (node (ref "V1") (pin "1") (pinfunction "-VIN_1") (pintype "passive"))
      (node (ref "X1") (pin "4") (pinfunction "4_4") (pintype "passive"))
    )
    (net (code "31") (name "N$12") (class "Default")
      (node (ref "C35") (pin "1") (pinfunction "1_1") (pintype "passive"))
      (node (ref "IC1") (pin "22") (pinfunction "RESET_22") (pintype "bidirectional"))
      (node (ref "R19") (pin "2") (pinfunction "2_2") (pintype "passive"))
    )
    (net (code "32") (name "Net-(C38-Pad1)") (class "Default")
      (node (ref "C38") (pin "1") (pinfunction "1_1") (pintype "passive"))
      (node (ref "C39") (pin "1") (pinfunction "1_1") (pintype "passive"))
      (node (ref "D2") (pin "C") (pinfunction "C_C") (pintype "passive"))
      (node (ref "IC1") (pin "30") (pinfunction "AVDD_30") (pintype "bidirectional"))
      (node (ref "IC1") (pin "41") (pinfunction "AVDD_41") (pintype "bidirectional"))
      (node (ref "L9") (pin "2") (pinfunction "2_2") (pintype "passive"))
    )
    (net (code "33") (name "Net-(C42-Pad1)") (class "Default")
      (node (ref "C42") (pin "1") (pinfunction "1_1") (pintype "passive"))
      (node (ref "R18") (pin "1") (pinfunction "1_1") (pintype "passive"))
    )
    (net (code "34") (name "Net-(C43-Pad1)") (class "Default")
      (node (ref "C43") (pin "1") (pinfunction "1_1") (pintype "passive"))
      (node (ref "R13") (pin "1") (pinfunction "1_1") (pintype "passive"))
      (node (ref "R7") (pin "2") (pinfunction "2_2") (pintype "passive"))
    )
    (net (code "35") (name "Net-(C44-Pad1)") (class "Default")
      (node (ref "C44") (pin "1") (pinfunction "1_1") (pintype "passive"))
      (node (ref "R12") (pin "1") (pinfunction "1_1") (pintype "passive"))
      (node (ref "R8") (pin "2") (pinfunction "2_2") (pintype "passive"))
    )
    (net (code "36") (name "Net-(C49-Pad1)") (class "Default")
      (node (ref "C49") (pin "1") (pinfunction "1_1") (pintype "passive"))
      (node (ref "R10") (pin "2") (pinfunction "2_2") (pintype "passive"))
      (node (ref "R2") (pin "1") (pinfunction "1_1") (pintype "passive"))
    )
    (net (code "37") (name "Net-(C50-Pad1)") (class "Default")
      (node (ref "C50") (pin "1") (pinfunction "1_1") (pintype "passive"))
      (node (ref "R1") (pin "1") (pinfunction "1_1") (pintype "passive"))
      (node (ref "R11") (pin "2") (pinfunction "2_2") (pintype "passive"))
    )
    (net (code "38") (name "Net-(D3-PadA)") (class "Default")
      (node (ref "D3") (pin "A") (pinfunction "A_A") (pintype "passive"))
      (node (ref "D4") (pin "C") (pinfunction "C_C") (pintype "passive"))
    )
    (net (code "39") (name "Net-(DISPLAYA-CLK)") (class "Default")
      (node (ref "DISPLAY") (pin "18") (pinfunction "CLK_18") (pintype "bidirectional"))
      (node (ref "DISPLAY") (pin "32") (pinfunction "CLK_32") (pintype "bidirectional"))
      (node (ref "IC6") (pin "30") (pinfunction "PA5_30") (pintype "bidirectional"))
    )
    (net (code "40") (name "Net-(DISPLAYA-DIN)") (class "Default")
      (node (ref "DISPLAY") (pin "22") (pinfunction "DIN_22") (pintype "bidirectional"))
      (node (ref "DISPLAY") (pin "34") (pinfunction "MOSI_34") (pintype "bidirectional"))
      (node (ref "IC6") (pin "32") (pinfunction "PA7_32") (pintype "bidirectional"))
    )
    (net (code "41") (name "Net-(DISPLAYA-DOUT)") (class "Default")
      (node (ref "DISPLAY") (pin "26") (pinfunction "DOUT_26") (pintype "bidirectional"))
      (node (ref "DISPLAY") (pin "30") (pinfunction "MISO_30") (pintype "bidirectional"))
      (node (ref "IC6") (pin "31") (pinfunction "PA6_31") (pintype "bidirectional"))
    )
    (net (code "42") (name "Net-(DISPLAYC-DB0)") (class "Default")
      (node (ref "DISPLAY") (pin "2") (pinfunction "DB0_2") (pintype "bidirectional"))
      (node (ref "IC6") (pin "97") (pinfunction "PE0_97") (pintype "bidirectional"))
    )
    (net (code "43") (name "Net-(DISPLAYC-DB1)") (class "Default")
      (node (ref "DISPLAY") (pin "4") (pinfunction "DB1_4") (pintype "bidirectional"))
      (node (ref "IC6") (pin "98") (pinfunction "PE1_98") (pintype "bidirectional"))
    )
    (net (code "44") (name "Net-(DISPLAYC-DB2)") (class "Default")
      (node (ref "DISPLAY") (pin "6") (pinfunction "DB2_6") (pintype "bidirectional"))
      (node (ref "IC6") (pin "1") (pinfunction "PE2_1") (pintype "bidirectional"))
    )
    (net (code "45") (name "Net-(DISPLAYC-DB3)") (class "Default")
      (node (ref "DISPLAY") (pin "8") (pinfunction "DB3_8") (pintype "bidirectional"))
      (node (ref "IC6") (pin "2") (pinfunction "PE3_2") (pintype "bidirectional"))
    )
    (net (code "46") (name "Net-(DISPLAYC-DB4)") (class "Default")
      (node (ref "DISPLAY") (pin "10") (pinfunction "DB4_10") (pintype "bidirectional"))
      (node (ref "IC6") (pin "3") (pinfunction "PE4_3") (pintype "bidirectional"))
    )
    (net (code "47") (name "Net-(DISPLAYC-DB5)") (class "Default")
      (node (ref "DISPLAY") (pin "12") (pinfunction "DB5_12") (pintype "bidirectional"))
      (node (ref "IC6") (pin "4") (pinfunction "PE5_4") (pintype "bidirectional"))
    )
    (net (code "48") (name "Net-(DISPLAYC-DB6)") (class "Default")
      (node (ref "DISPLAY") (pin "14") (pinfunction "DB6_14") (pintype "bidirectional"))
      (node (ref "IC6") (pin "5") (pinfunction "PE6_5") (pintype "bidirectional"))
    )
    (net (code "49") (name "Net-(DISPLAYC-DB7)") (class "Default")
      (node (ref "DISPLAY") (pin "16") (pinfunction "DB7_16") (pintype "bidirectional"))
      (node (ref "IC6") (pin "38") (pinfunction "PE7_38") (pintype "bidirectional"))
    )
    (net (code "50") (name "Net-(DISPLAYC-DB8)") (class "Default")
      (node (ref "DISPLAY") (pin "13") (pinfunction "DB8_13") (pintype "bidirectional"))
      (node (ref "IC6") (pin "39") (pinfunction "PE8_39") (pintype "bidirectional"))
    )
    (net (code "51") (name "Net-(DISPLAYC-DB9)") (class "Default")
      (node (ref "DISPLAY") (pin "15") (pinfunction "DB9_15") (pintype "bidirectional"))
      (node (ref "IC6") (pin "40") (pinfunction "PE9_40") (pintype "bidirectional"))
    )
    (net (code "52") (name "Net-(DISPLAYC-DB10)") (class "Default")
      (node (ref "DISPLAY") (pin "17") (pinfunction "DB10_17") (pintype "bidirectional"))
      (node (ref "IC6") (pin "41") (pinfunction "PE10_41") (pintype "bidirectional"))
    )
    (net (code "53") (name "Net-(DISPLAYC-DB11)") (class "Default")
      (node (ref "DISPLAY") (pin "19") (pinfunction "DB11_19") (pintype "bidirectional"))
      (node (ref "IC6") (pin "42") (pinfunction "PE11_42") (pintype "bidirectional"))
    )
    (net (code "54") (name "Net-(DISPLAYC-DB12)") (class "Default")
      (node (ref "DISPLAY") (pin "21") (pinfunction "DB12_21") (pintype "bidirectional"))
      (node (ref "IC6") (pin "43") (pinfunction "PE12_43") (pintype "bidirectional"))
    )
    (net (code "55") (name "Net-(DISPLAYC-DB13)") (class "Default")
      (node (ref "DISPLAY") (pin "23") (pinfunction "DB13_23") (pintype "bidirectional"))
      (node (ref "IC6") (pin "44") (pinfunction "PE13_44") (pintype "bidirectional"))
    )
    (net (code "56") (name "Net-(DISPLAYC-DB14)") (class "Default")
      (node (ref "DISPLAY") (pin "25") (pinfunction "DB14_25") (pintype "bidirectional"))
      (node (ref "IC6") (pin "45") (pinfunction "PE14_45") (pintype "bidirectional"))
    )
    (net (code "57") (name "Net-(DISPLAYC-DB15)") (class "Default")
      (node (ref "DISPLAY") (pin "27") (pinfunction "DB15_27") (pintype "bidirectional"))
      (node (ref "IC6") (pin "46") (pinfunction "PE15_46") (pintype "bidirectional"))
    )
    (net (code "58") (name "Net-(DISPLAYD-LED_A+)") (class "Default")
      (node (ref "DISPLAY") (pin "37") (pinfunction "LED_A+_37") (pintype "bidirectional"))
      (node (ref "R30") (pin "1") (pinfunction "1_1") (pintype "passive"))
    )
    (net (code "59") (name "Net-(I+-P)") (class "Default")
      (node (ref "C42") (pin "2") (pinfunction "2_2") (pintype "passive"))
      (node (ref "I+") (pin "1") (pinfunction "P_1") (pintype "passive"))
      (node (ref "R15") (pin "1") (pinfunction "1_1") (pintype "passive"))
      (node (ref "R17") (pin "1") (pinfunction "1_1") (pintype "passive"))
      (node (ref "R4") (pin "1") (pinfunction "1_1") (pintype "passive"))
    )
    (net (code "60") (name "Net-(I--P)") (class "Default")
      (node (ref "I-") (pin "1") (pinfunction "P_1") (pintype "passive"))
      (node (ref "R3") (pin "1") (pinfunction "1_1") (pintype "passive"))
    )
    (net (code "61") (name "Net-(IC1-AFE1)") (class "Default")
      (node (ref "C49") (pin "2") (pinfunction "2_2") (pintype "passive"))
      (node (ref "IC1") (pin "33") (pinfunction "RCAL1_33") (pintype "bidirectional"))
      (node (ref "IC1") (pin "34") (pinfunction "AFE1_34") (pintype "bidirectional"))
      (node (ref "R9") (pin "1") (pinfunction "1_1") (pintype "passive"))
    )
    (net (code "62") (name "Net-(IC1-AFE2)") (class "Default")
      (node (ref "D4") (pin "A") (pinfunction "A_A") (pintype "passive"))
      (node (ref "IC1") (pin "35") (pinfunction "AFE2_35") (pintype "bidirectional"))
      (node (ref "R4") (pin "2") (pinfunction "2_2") (pintype "passive"))
    )
    (net (code "63") (name "Net-(IC1-AIN0)") (class "Default")
      (node (ref "IC1") (pin "39") (pinfunction "AIN0_39") (pintype "bidirectional"))
      (node (ref "R7") (pin "1") (pinfunction "1_1") (pintype "passive"))
    )
    (net (code "64") (name "Net-(IC1-AIN1)") (class "Default")
      (node (ref "IC1") (pin "38") (pinfunction "AIN1_38") (pintype "bidirectional"))
      (node (ref "R8") (pin "1") (pinfunction "1_1") (pintype "passive"))
    )
    (net (code "65") (name "Net-(IC1-AIN2)") (class "Default")
      (node (ref "IC1") (pin "37") (pinfunction "AIN2_37") (pintype "bidirectional"))
      (node (ref "R10") (pin "1") (pinfunction "1_1") (pintype "passive"))
    )
    (net (code "66") (name "Net-(IC1-AIN3{slash}BUF_VREF1V8)") (class "Default")
      (node (ref "IC1") (pin "36") (pinfunction "AIN3/BUF_VREF1V8_36") (pintype "bidirectional"))
      (node (ref "R11") (pin "1") (pinfunction "1_1") (pintype "passive"))
    )
    (net (code "67") (name "Net-(IC1-AIN4{slash}LPF0)") (class "Default")
      (node (ref "C50") (pin "2") (pinfunction "2_2") (pintype "passive"))
      (node (ref "IC1") (pin "32") (pinfunction "RCAL0_32") (pintype "bidirectional"))
      (node (ref "IC1") (pin "40") (pinfunction "AIN4/LPF0_40") (pintype "bidirectional"))
      (node (ref "R9") (pin "2") (pinfunction "2_2") (pintype "passive"))
    )
    (net (code "68") (name "Net-(IC1-AVDD_REG)") (class "Default")
      (node (ref "C9") (pin "1") (pinfunction "1_1") (pintype "passive"))
      (node (ref "IC1") (pin "5") (pinfunction "AVDD_REG_5") (pintype "bidirectional"))
    )
    (net (code "69") (name "Net-(IC1-CE0)") (class "Default")
      (node (ref "IC1") (pin "47") (pinfunction "CE0_47") (pintype "bidirectional"))
      (node (ref "R18") (pin "2") (pinfunction "2_2") (pintype "passive"))
    )
    (net (code "70") (name "Net-(IC1-CS)") (class "Default")
      (node (ref "IC1") (pin "15") (pinfunction "CS_15") (pintype "bidirectional"))
      (node (ref "IC4") (pin "14") (pinfunction "VOA_14") (pintype "output"))
    )
    (net (code "71") (name "Net-(IC1-DE0)") (class "Default")
      (node (ref "D1") (pin "C") (pinfunction "C_C") (pintype "passive"))
      (node (ref "D2") (pin "A") (pinfunction "A_A") (pintype "passive"))
      (node (ref "IC1") (pin "46") (pinfunction "DE0_46") (pintype "bidirectional"))
      (node (ref "R3") (pin "2") (pinfunction "2_2") (pintype "passive"))
    )
    (net (code "72") (name "Net-(IC1-DVDD_REG_1V8)") (class "Default")
      (node (ref "C10") (pin "1") (pinfunction "1_1") (pintype "passive"))
      (node (ref "IC1") (pin "14") (pinfunction "DVDD_REG_1V8_14") (pintype "bidirectional"))
    )
    (net (code "73") (name "Net-(IC1-MISO)") (class "Default")
      (node (ref "IC1") (pin "18") (pinfunction "MISO_18") (pintype "bidirectional"))
      (node (ref "IC4") (pin "11") (pinfunction "VID_11") (pintype "input"))
    )
    (net (code "74") (name "Net-(IC1-MOSI)") (class "Default")
      (node (ref "IC1") (pin "17") (pinfunction "MOSI_17") (pintype "bidirectional"))
      (node (ref "IC4") (pin "12") (pinfunction "VOC_12") (pintype "output"))
    )
    (net (code "75") (name "Net-(IC1-RE0)") (class "Default")
      (node (ref "IC1") (pin "48") (pinfunction "RE0_48") (pintype "bidirectional"))
      (node (ref "R16") (pin "2") (pinfunction "2_2") (pintype "passive"))
    )
    (net (code "76") (name "Net-(IC1-SCLK)") (class "Default")
      (node (ref "IC1") (pin "16") (pinfunction "SCLK_16") (pintype "bidirectional"))
      (node (ref "IC4") (pin "13") (pinfunction "VOB_13") (pintype "output"))
    )
    (net (code "77") (name "Net-(IC1-VBIAS0)") (class "Default")
      (node (ref "C11") (pin "1") (pinfunction "1_1") (pintype "passive"))
      (node (ref "IC1") (pin "8") (pinfunction "VBIAS0_8") (pintype "bidirectional"))
    )
    (net (code "78") (name "Net-(IC1-VBIAS_CAP)") (class "Default")
      (node (ref "C1") (pin "1") (pinfunction "1_1") (pintype "passive"))
      (node (ref "IC1") (pin "31") (pinfunction "VBIAS_CAP_31") (pintype "bidirectional"))
      (node (ref "R1") (pin "2") (pinfunction "2_2") (pintype "passive"))
      (node (ref "R12") (pin "2") (pinfunction "2_2") (pintype "passive"))
      (node (ref "R13") (pin "2") (pinfunction "2_2") (pintype "passive"))
      (node (ref "R2") (pin "2") (pinfunction "2_2") (pintype "passive"))
    )
    (net (code "79") (name "Net-(IC1-VREF_1V8)") (class "Default")
      (node (ref "C5") (pin "1") (pinfunction "1_1") (pintype "passive"))
      (node (ref "IC1") (pin "43") (pinfunction "VREF_1V8_43") (pintype "bidirectional"))
    )
    (net (code "80") (name "Net-(IC1-VREF_2V5)") (class "Default")
      (node (ref "C6") (pin "1") (pinfunction "1_1") (pintype "passive"))
      (node (ref "IC1") (pin "4") (pinfunction "VREF_2V5_4") (pintype "bidirectional"))
    )
    (net (code "81") (name "Net-(IC1-VZERO0)") (class "Default")
      (node (ref "C12") (pin "1") (pinfunction "1_1") (pintype "passive"))
      (node (ref "IC1") (pin "9") (pinfunction "VZERO0_9") (pintype "bidirectional"))
    )
    (net (code "82") (name "Net-(IC1-XTALI)") (class "Default")
      (node (ref "C13") (pin "1") (pinfunction "1_1") (pintype "passive"))
      (node (ref "IC1") (pin "11") (pinfunction "XTALI_11") (pintype "bidirectional"))
      (node (ref "Q1") (pin "1") (pinfunction "1_1") (pintype "passive"))
    )
    (net (code "83") (name "Net-(IC1-XTALO)") (class "Default")
      (node (ref "C16") (pin "1") (pinfunction "1_1") (pintype "passive"))
      (node (ref "IC1") (pin "12") (pinfunction "XTALO_12") (pintype "bidirectional"))
      (node (ref "Q1") (pin "3") (pinfunction "3_3") (pintype "passive"))
    )
    (net (code "84") (name "Net-(IC6A-NRST)") (class "Default")
      (node (ref "C25") (pin "1") (pinfunction "1_1") (pintype "passive"))
      (node (ref "IC6") (pin "14") (pinfunction "NRST_14") (pintype "bidirectional"))
      (node (ref "R29") (pin "2") (pinfunction "2_2") (pintype "passive"))
      (node (ref "SWD") (pin "3") (pinfunction "3_3") (pintype "passive"))
    )
    (net (code "85") (name "Net-(IC6A-OSC_IN)") (class "Default")
      (node (ref "C14") (pin "1") (pinfunction "1_1") (pintype "passive"))
      (node (ref "IC6") (pin "12") (pinfunction "OSC_IN_12") (pintype "bidirectional"))
      (node (ref "Q3") (pin "1") (pinfunction "1_1") (pintype "passive"))
    )
    (net (code "86") (name "Net-(IC6A-OSC_OUT)") (class "Default")
      (node (ref "C15") (pin "1") (pinfunction "1_1") (pintype "passive"))
      (node (ref "IC6") (pin "13") (pinfunction "OSC_OUT_13") (pintype "bidirectional"))
      (node (ref "Q3") (pin "3") (pinfunction "3_3") (pintype "passive"))
    )
    (net (code "87") (name "Net-(IC6A-PA9)") (class "Default")
      (node (ref "IC6") (pin "68") (pinfunction "PA9_68") (pintype "bidirectional"))
      (node (ref "UART") (pin "3") (pinfunction "3_3") (pintype "passive"))
    )
    (net (code "88") (name "Net-(IC6A-PA10)") (class "Default")
      (node (ref "IC6") (pin "69") (pinfunction "PA10_69") (pintype "bidirectional"))
      (node (ref "UART") (pin "1") (pinfunction "1_1") (pintype "passive"))
    )
    (net (code "89") (name "Net-(IC6A-PB8)") (class "Default")
      (node (ref "IC6") (pin "95") (pinfunction "PB8_95") (pintype "bidirectional"))
      (node (ref "Q2") (pin "1") (pinfunction "G_1") (pintype "passive"))
    )
    (net (code "90") (name "Net-(IC7-+IN)") (class "Default")
      (node (ref "C52") (pin "2") (pinfunction "2_2") (pintype "passive"))
      (node (ref "IC7") (pin "3") (pinfunction "+IN_3") (pintype "input"))
      (node (ref "R16") (pin "1") (pinfunction "1_1") (pintype "passive"))
    )
    (net (code "91") (name "Net-(IC7--IN)") (class "Default")
      (node (ref "C51") (pin "1") (pinfunction "1_1") (pintype "passive"))
      (node (ref "IC7") (pin "4") (pinfunction "-IN_4") (pintype "input"))
      (node (ref "R14") (pin "2") (pinfunction "2_2") (pintype "passive"))
      (node (ref "R15") (pin "2") (pinfunction "2_2") (pintype "passive"))
    )
    (net (code "92") (name "Net-(IC7-OUT)") (class "Default")
      (node (ref "C51") (pin "2") (pinfunction "2_2") (pintype "passive"))
      (node (ref "IC7") (pin "1") (pinfunction "OUT_1") (pintype "output"))
      (node (ref "R17") (pin "2") (pinfunction "2_2") (pintype "passive"))
    )
    (net (code "93") (name "Net-(L1-2)") (class "Default")
      (node (ref "C3") (pin "1") (pinfunction "1_1") (pintype "passive"))
      (node (ref "L1") (pin "P$2") (pinfunction "2_P$2") (pintype "passive"))
      (node (ref "V1") (pin "2") (pinfunction "+VIN_2") (pintype "passive"))
    )
    (net (code "94") (name "Net-(L2-1)") (class "Default")
      (node (ref "C7") (pin "1") (pinfunction "1_1") (pintype "passive"))
      (node (ref "L2") (pin "P$1") (pinfunction "1_P$1") (pintype "passive"))
      (node (ref "V1") (pin "4") (pinfunction "+VOUT_4") (pintype "passive"))
    )
    (net (code "95") (name "Net-(L2-2)") (class "Default")
      (node (ref "L2") (pin "P$2") (pinfunction "2_P$2") (pintype "passive"))
      (node (ref "L3") (pin "1") (pinfunction "1_1") (pintype "passive"))
    )
    (net (code "96") (name "Net-(L4-1)") (class "Default")
      (node (ref "C2") (pin "1") (pinfunction "1_1") (pintype "passive"))
      (node (ref "C7") (pin "2") (pinfunction "2_2") (pintype "passive"))
      (node (ref "L4") (pin "P$1") (pinfunction "1_P$1") (pintype "passive"))
      (node (ref "V1") (pin "3") (pinfunction "-VOUT_3") (pintype "passive"))
    )
    (net (code "97") (name "Net-(L4-2)") (class "Default")
      (node (ref "L4") (pin "P$2") (pinfunction "2_P$2") (pintype "passive"))
      (node (ref "L5") (pin "1") (pinfunction "1_1") (pintype "passive"))
    )
    (net (code "98") (name "Net-(Q2-D)") (class "Default")
      (node (ref "D5") (pin "A") (pinfunction "A_A") (pintype "passive"))
      (node (ref "Q2") (pin "3") (pinfunction "D_3") (pintype "passive"))
      (node (ref "SG1") (pin "-") (pinfunction "+_-") (pintype "passive"))
    )
    (net (code "99") (name "Net-(R21-Pad2)") (class "Default")
      (node (ref "R21") (pin "2") (pinfunction "2_2") (pintype "passive"))
      (node (ref "U1") (pin "3") (pinfunction "IO2_3") (pintype "bidirectional"))
    )
    (net (code "100") (name "Net-(R22-Pad2)") (class "Default")
      (node (ref "R22") (pin "2") (pinfunction "2_2") (pintype "passive"))
      (node (ref "U1") (pin "1") (pinfunction "IO1_1") (pintype "bidirectional"))
    )
    (net (code "101") (name "Net-(SG1--)") (class "Default")
      (node (ref "D5") (pin "C") (pinfunction "C_C") (pintype "passive"))
      (node (ref "R6") (pin "1") (pinfunction "1_1") (pintype "passive"))
      (node (ref "SG1") (pin "+") (pinfunction "-_+") (pintype "passive"))
    )
    (net (code "102") (name "Net-(U+-P)") (class "Default")
      (node (ref "C43") (pin "2") (pinfunction "2_2") (pintype "passive"))
      (node (ref "U+") (pin "1") (pinfunction "P_1") (pintype "passive"))
    )
    (net (code "103") (name "Net-(U--P)") (class "Default")
      (node (ref "C44") (pin "2") (pinfunction "2_2") (pintype "passive"))
      (node (ref "U-") (pin "1") (pinfunction "P_1") (pintype "passive"))
    )
    (net (code "104") (name "Net-(U1-IO1-Pad6)") (class "Default")
      (node (ref "U1") (pin "6") (pinfunction "IO1_6") (pintype "bidirectional"))
      (node (ref "X1") (pin "3") (pinfunction "3_3") (pintype "passive"))
    )
    (net (code "105") (name "Net-(U1-IO2-Pad4)") (class "Default")
      (node (ref "U1") (pin "4") (pinfunction "IO2_4") (pintype "bidirectional"))
      (node (ref "X1") (pin "2") (pinfunction "2_2") (pintype "passive"))
    )
    (net (code "106") (name "Net-(U1-VBUS)") (class "Default")
      (node (ref "JP1") (pin "2") (pinfunction "2_2") (pintype "passive"))
      (node (ref "U1") (pin "5") (pinfunction "VBUS_5") (pintype "power_in"))
      (node (ref "X1") (pin "1") (pinfunction "1_1") (pintype "passive"))
    )
    (net (code "107") (name "SD_CS") (class "Default")
      (node (ref "DISPLAY") (pin "36") (pinfunction "CS_36") (pintype "bidirectional"))
      (node (ref "IC6") (pin "26") (pinfunction "PA3_26") (pintype "bidirectional"))
    )
    (net (code "108") (name "SWCLK") (class "Default")
      (node (ref "IC6") (pin "76") (pinfunction "PA14_76") (pintype "bidirectional"))
      (node (ref "SWD") (pin "2") (pinfunction "2_2") (pintype "passive"))
    )
    (net (code "109") (name "SWDIO") (class "Default")
      (node (ref "IC6") (pin "72") (pinfunction "PA13_72") (pintype "bidirectional"))
      (node (ref "SWD") (pin "4") (pinfunction "4_4") (pintype "passive"))
    )
    (net (code "110") (name "TFT_CS") (class "Default")
      (node (ref "DISPLAY") (pin "29") (pinfunction "CS_29") (pintype "bidirectional"))
      (node (ref "IC6") (pin "24") (pinfunction "PA1_24") (pintype "bidirectional"))
    )
    (net (code "111") (name "TFT_RD") (class "Default")
      (node (ref "DISPLAY") (pin "11") (pinfunction "RD_11") (pintype "bidirectional"))
      (node (ref "IC6") (pin "9") (pinfunction "PC15_9") (pintype "bidirectional"))
    )
    (net (code "112") (name "TFT_RS") (class "Default")
      (node (ref "DISPLAY") (pin "7") (pinfunction "RS_7") (pintype "bidirectional"))
      (node (ref "IC6") (pin "7") (pinfunction "PC13_7") (pintype "bidirectional"))
    )
    (net (code "113") (name "TFT_RST") (class "Default")
      (node (ref "DISPLAY") (pin "33") (pinfunction "RST_33") (pintype "bidirectional"))
      (node (ref "IC6") (pin "25") (pinfunction "PA2_25") (pintype "bidirectional"))
    )
    (net (code "114") (name "TFT_WR") (class "Default")
      (node (ref "DISPLAY") (pin "9") (pinfunction "WR_9") (pintype "bidirectional"))
      (node (ref "IC6") (pin "8") (pinfunction "PC14_8") (pintype "bidirectional"))
    )
    (net (code "115") (name "TOUCH_CS") (class "Default")
      (node (ref "DISPLAY") (pin "20") (pinfunction "CS_20") (pintype "bidirectional"))
      (node (ref "IC6") (pin "10") (pinfunction "PF9_10") (pintype "bidirectional"))
    )
    (net (code "116") (name "TOUCH_IRQ") (class "Default")
      (node (ref "DISPLAY") (pin "28") (pinfunction "IRQ_28") (pintype "bidirectional"))
      (node (ref "IC6") (pin "23") (pinfunction "PA0-WKUP_23") (pintype "bidirectional"))
    )
    (net (code "117") (name "USB_IDENT") (class "Default")
      (node (ref "IC6") (pin "67") (pinfunction "PA8_67") (pintype "bidirectional"))
      (node (ref "R5") (pin "2") (pinfunction "2_2") (pintype "passive"))
    )
    (net (code "118") (name "USB_N") (class "Default")
      (node (ref "IC6") (pin "70") (pinfunction "PA11_70") (pintype "bidirectional"))
      (node (ref "R21") (pin "1") (pinfunction "1_1") (pintype "passive"))
    )
    (net (code "119") (name "USB_P") (class "Default")
      (node (ref "IC6") (pin "71") (pinfunction "PA12_71") (pintype "bidirectional"))
      (node (ref "R20") (pin "2") (pinfunction "2_2") (pintype "passive"))
      (node (ref "R22") (pin "1") (pinfunction "1_1") (pintype "passive"))
      (node (ref "R5") (pin "1") (pinfunction "1_1") (pintype "passive"))
    )
    (net (code "120") (name "VCC") (class "Default")
      (node (ref "C17") (pin "1") (pinfunction "1_1") (pintype "passive"))
      (node (ref "C18") (pin "1") (pinfunction "1_1") (pintype "passive"))
      (node (ref "C27") (pin "1") (pinfunction "1_1") (pintype "passive"))
      (node (ref "C31") (pin "1") (pinfunction "1_1") (pintype "passive"))
      (node (ref "C34") (pin "1") (pinfunction "1_1") (pintype "passive"))
      (node (ref "IC1") (pin "26") (pinfunction "IOVDD_26") (pintype "bidirectional"))
      (node (ref "IC1") (pin "6") (pinfunction "DVDD_6") (pintype "bidirectional"))
      (node (ref "IC2") (pin "2") (pinfunction "VOUT_2") (pintype "power_in"))
      (node (ref "IC2") (pin "4") (pinfunction "VOUT_4") (pintype "power_in"))
      (node (ref "IC4") (pin "10") (pinfunction "VE2_10") (pintype "passive"))
      (node (ref "IC4") (pin "16") (pinfunction "VDD2_16") (pintype "power_in"))
      (node (ref "L9") (pin "1") (pinfunction "1_1") (pintype "passive"))
      (node (ref "R19") (pin "1") (pinfunction "1_1") (pintype "passive"))
    )
    (net (code "121") (name "unconnected-(DISPLAYA-BUSY-Pad24)") (class "Default")
      (node (ref "DISPLAY") (pin "24") (pinfunction "BUSY_24") (pintype "bidirectional"))
    )
    (net (code "122") (name "unconnected-(IC1-AFE3-Pad27)") (class "Default")
      (node (ref "IC1") (pin "27") (pinfunction "AFE3_27") (pintype "bidirectional"))
    )
    (net (code "123") (name "unconnected-(IC1-AFE4-Pad28)") (class "Default")
      (node (ref "IC1") (pin "28") (pinfunction "AFE4_28") (pintype "bidirectional"))
    )
    (net (code "124") (name "unconnected-(IC1-GPIO0-Pad19)") (class "Default")
      (node (ref "IC1") (pin "19") (pinfunction "GPIO0_19") (pintype "bidirectional"))
    )
    (net (code "125") (name "unconnected-(IC1-GPIO1-Pad20)") (class "Default")
      (node (ref "IC1") (pin "20") (pinfunction "GPIO1_20") (pintype "bidirectional"))
    )
    (net (code "126") (name "unconnected-(IC1-GPIO2-Pad21)") (class "Default")
      (node (ref "IC1") (pin "21") (pinfunction "GPIO2_21") (pintype "bidirectional"))
    )
    (net (code "127") (name "unconnected-(IC1-RC0_0-Pad3)") (class "Default")
      (node (ref "IC1") (pin "3") (pinfunction "RC0_0_3") (pintype "bidirectional"))
    )
    (net (code "128") (name "unconnected-(IC1-RC0_1-Pad2)") (class "Default")
      (node (ref "IC1") (pin "2") (pinfunction "RC0_1_2") (pintype "bidirectional"))
    )
    (net (code "129") (name "unconnected-(IC1-RC0_2-Pad1)") (class "Default")
      (node (ref "IC1") (pin "1") (pinfunction "RC0_2_1") (pintype "bidirectional"))
    )
    (net (code "130") (name "unconnected-(IC1-SE0-Pad45)") (class "Default")
      (node (ref "IC1") (pin "45") (pinfunction "SE0_45") (pintype "bidirectional"))
    )
    (net (code "131") (name "unconnected-(IC6A-PA4-Pad29)") (class "Default")
      (node (ref "IC6") (pin "29") (pinfunction "PA4_29") (pintype "bidirectional"))
    )
    (net (code "132") (name "unconnected-(IC6A-PA15-Pad77)") (class "Default")
      (node (ref "IC6") (pin "77") (pinfunction "PA15_77") (pintype "bidirectional"))
    )
    (net (code "133") (name "unconnected-(IC6A-PB0-Pad35)") (class "Default")
      (node (ref "IC6") (pin "35") (pinfunction "PB0_35") (pintype "bidirectional"))
    )
    (net (code "134") (name "unconnected-(IC6A-PB9-Pad96)") (class "Default")
      (node (ref "IC6") (pin "96") (pinfunction "PB9_96") (pintype "bidirectional"))
    )
    (net (code "135") (name "unconnected-(IC6A-PC0-Pad15)") (class "Default")
      (node (ref "IC6") (pin "15") (pinfunction "PC0_15") (pintype "bidirectional"))
    )
    (net (code "136") (name "unconnected-(IC6A-PC1-Pad16)") (class "Default")
      (node (ref "IC6") (pin "16") (pinfunction "PC1_16") (pintype "bidirectional"))
    )
    (net (code "137") (name "unconnected-(IC6A-PC2-Pad17)") (class "Default")
      (node (ref "IC6") (pin "17") (pinfunction "PC2_17") (pintype "bidirectional"))
    )
    (net (code "138") (name "unconnected-(IC6A-PC3-Pad18)") (class "Default")
      (node (ref "IC6") (pin "18") (pinfunction "PC3_18") (pintype "bidirectional"))
    )
    (net (code "139") (name "unconnected-(IC6A-PC4-Pad33)") (class "Default")
      (node (ref "IC6") (pin "33") (pinfunction "PC4_33") (pintype "bidirectional"))
    )
    (net (code "140") (name "unconnected-(IC6A-PC5-Pad34)") (class "Default")
      (node (ref "IC6") (pin "34") (pinfunction "PC5_34") (pintype "bidirectional"))
    )
    (net (code "141") (name "unconnected-(IC6A-PC10-Pad78)") (class "Default")
      (node (ref "IC6") (pin "78") (pinfunction "PC10_78") (pintype "bidirectional"))
    )
    (net (code "142") (name "unconnected-(IC6A-PC11-Pad79)") (class "Default")
      (node (ref "IC6") (pin "79") (pinfunction "PC11_79") (pintype "bidirectional"))
    )
    (net (code "143") (name "unconnected-(IC6A-PC12-Pad80)") (class "Default")
      (node (ref "IC6") (pin "80") (pinfunction "PC12_80") (pintype "bidirectional"))
    )
    (net (code "144") (name "unconnected-(IC6A-PD0-Pad81)") (class "Default")
      (node (ref "IC6") (pin "81") (pinfunction "PD0_81") (pintype "bidirectional"))
    )
    (net (code "145") (name "unconnected-(IC6A-PD1-Pad82)") (class "Default")
      (node (ref "IC6") (pin "82") (pinfunction "PD1_82") (pintype "bidirectional"))
    )
    (net (code "146") (name "unconnected-(IC6A-PD2-Pad83)") (class "Default")
      (node (ref "IC6") (pin "83") (pinfunction "PD2_83") (pintype "bidirectional"))
    )
    (net (code "147") (name "unconnected-(IC6A-PD3-Pad84)") (class "Default")
      (node (ref "IC6") (pin "84") (pinfunction "PD3_84") (pintype "bidirectional"))
    )
    (net (code "148") (name "unconnected-(IC6A-PD4-Pad85)") (class "Default")
      (node (ref "IC6") (pin "85") (pinfunction "PD4_85") (pintype "bidirectional"))
    )
    (net (code "149") (name "unconnected-(IC6A-PD5-Pad86)") (class "Default")
      (node (ref "IC6") (pin "86") (pinfunction "PD5_86") (pintype "bidirectional"))
    )
    (net (code "150") (name "unconnected-(IC6A-PD6-Pad87)") (class "Default")
      (node (ref "IC6") (pin "87") (pinfunction "PD6_87") (pintype "bidirectional"))
    )
    (net (code "151") (name "unconnected-(IC6A-PD7-Pad88)") (class "Default")
      (node (ref "IC6") (pin "88") (pinfunction "PD7_88") (pintype "bidirectional"))
    )
    (net (code "152") (name "unconnected-(IC6A-PF2-Pad19)") (class "Default")
      (node (ref "IC6") (pin "19") (pinfunction "PF2_19") (pintype "bidirectional"))
    )
    (net (code "153") (name "unconnected-(IC6A-PF4-Pad27)") (class "Default")
      (node (ref "IC6") (pin "27") (pinfunction "PF4_27") (pintype "bidirectional"))
    )
    (net (code "154") (name "unconnected-(IC6A-PF6-Pad73)") (class "Default")
      (node (ref "IC6") (pin "73") (pinfunction "PF6_73") (pintype "bidirectional"))
    )
    (net (code "155") (name "unconnected-(IC6A-PF10-Pad11)") (class "Default")
      (node (ref "IC6") (pin "11") (pinfunction "PF10_11") (pintype "bidirectional"))
    )
  )
)
